# PiPod_Rev2.net
KiCad netlist of a schematic drawn in EAGLE
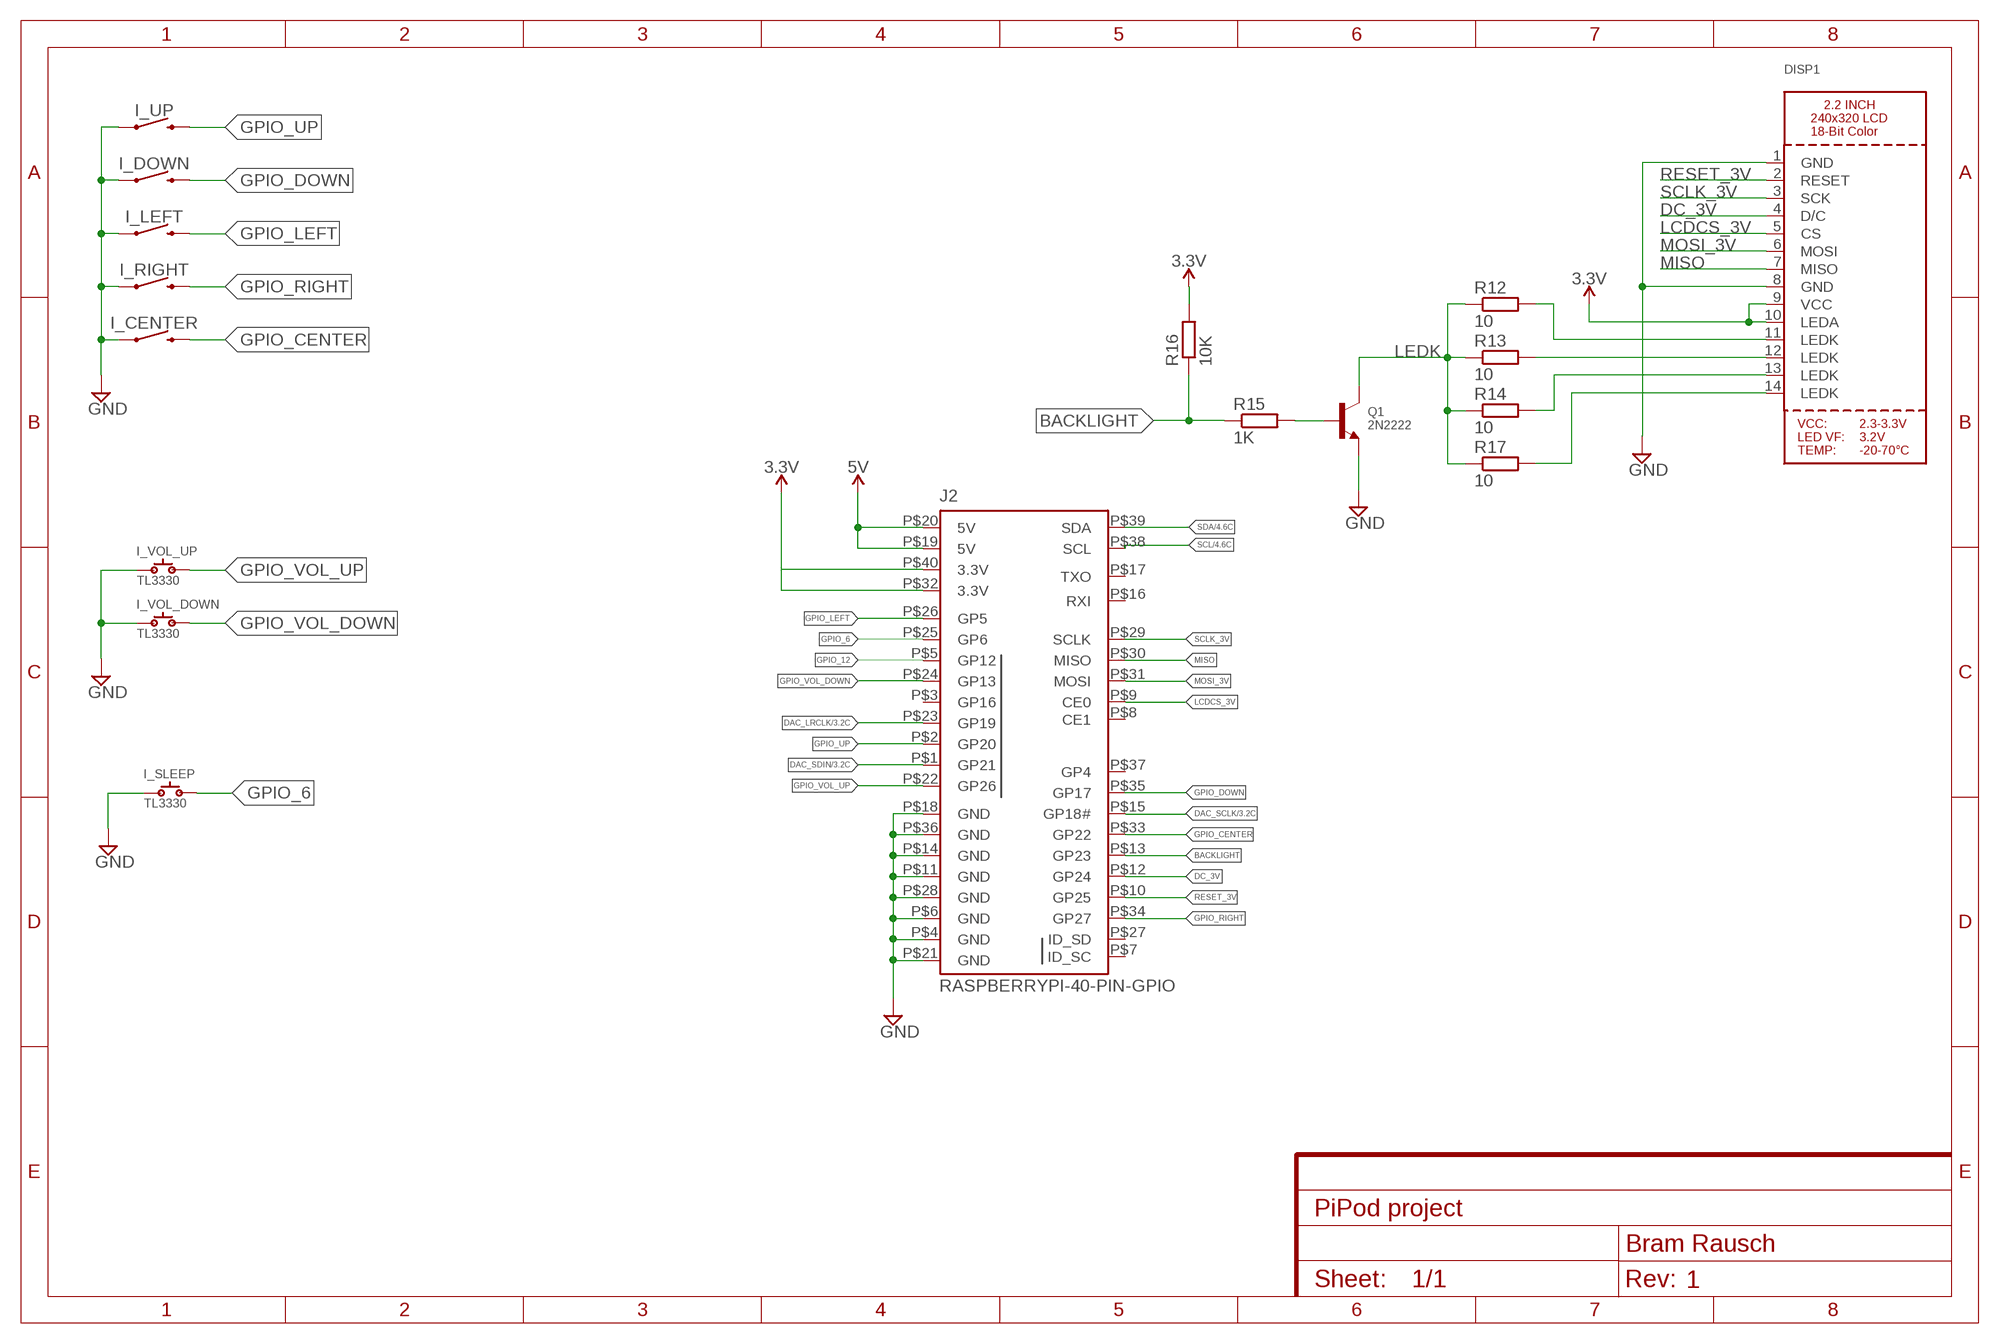
[diagram p0: schematic, sheet 1]
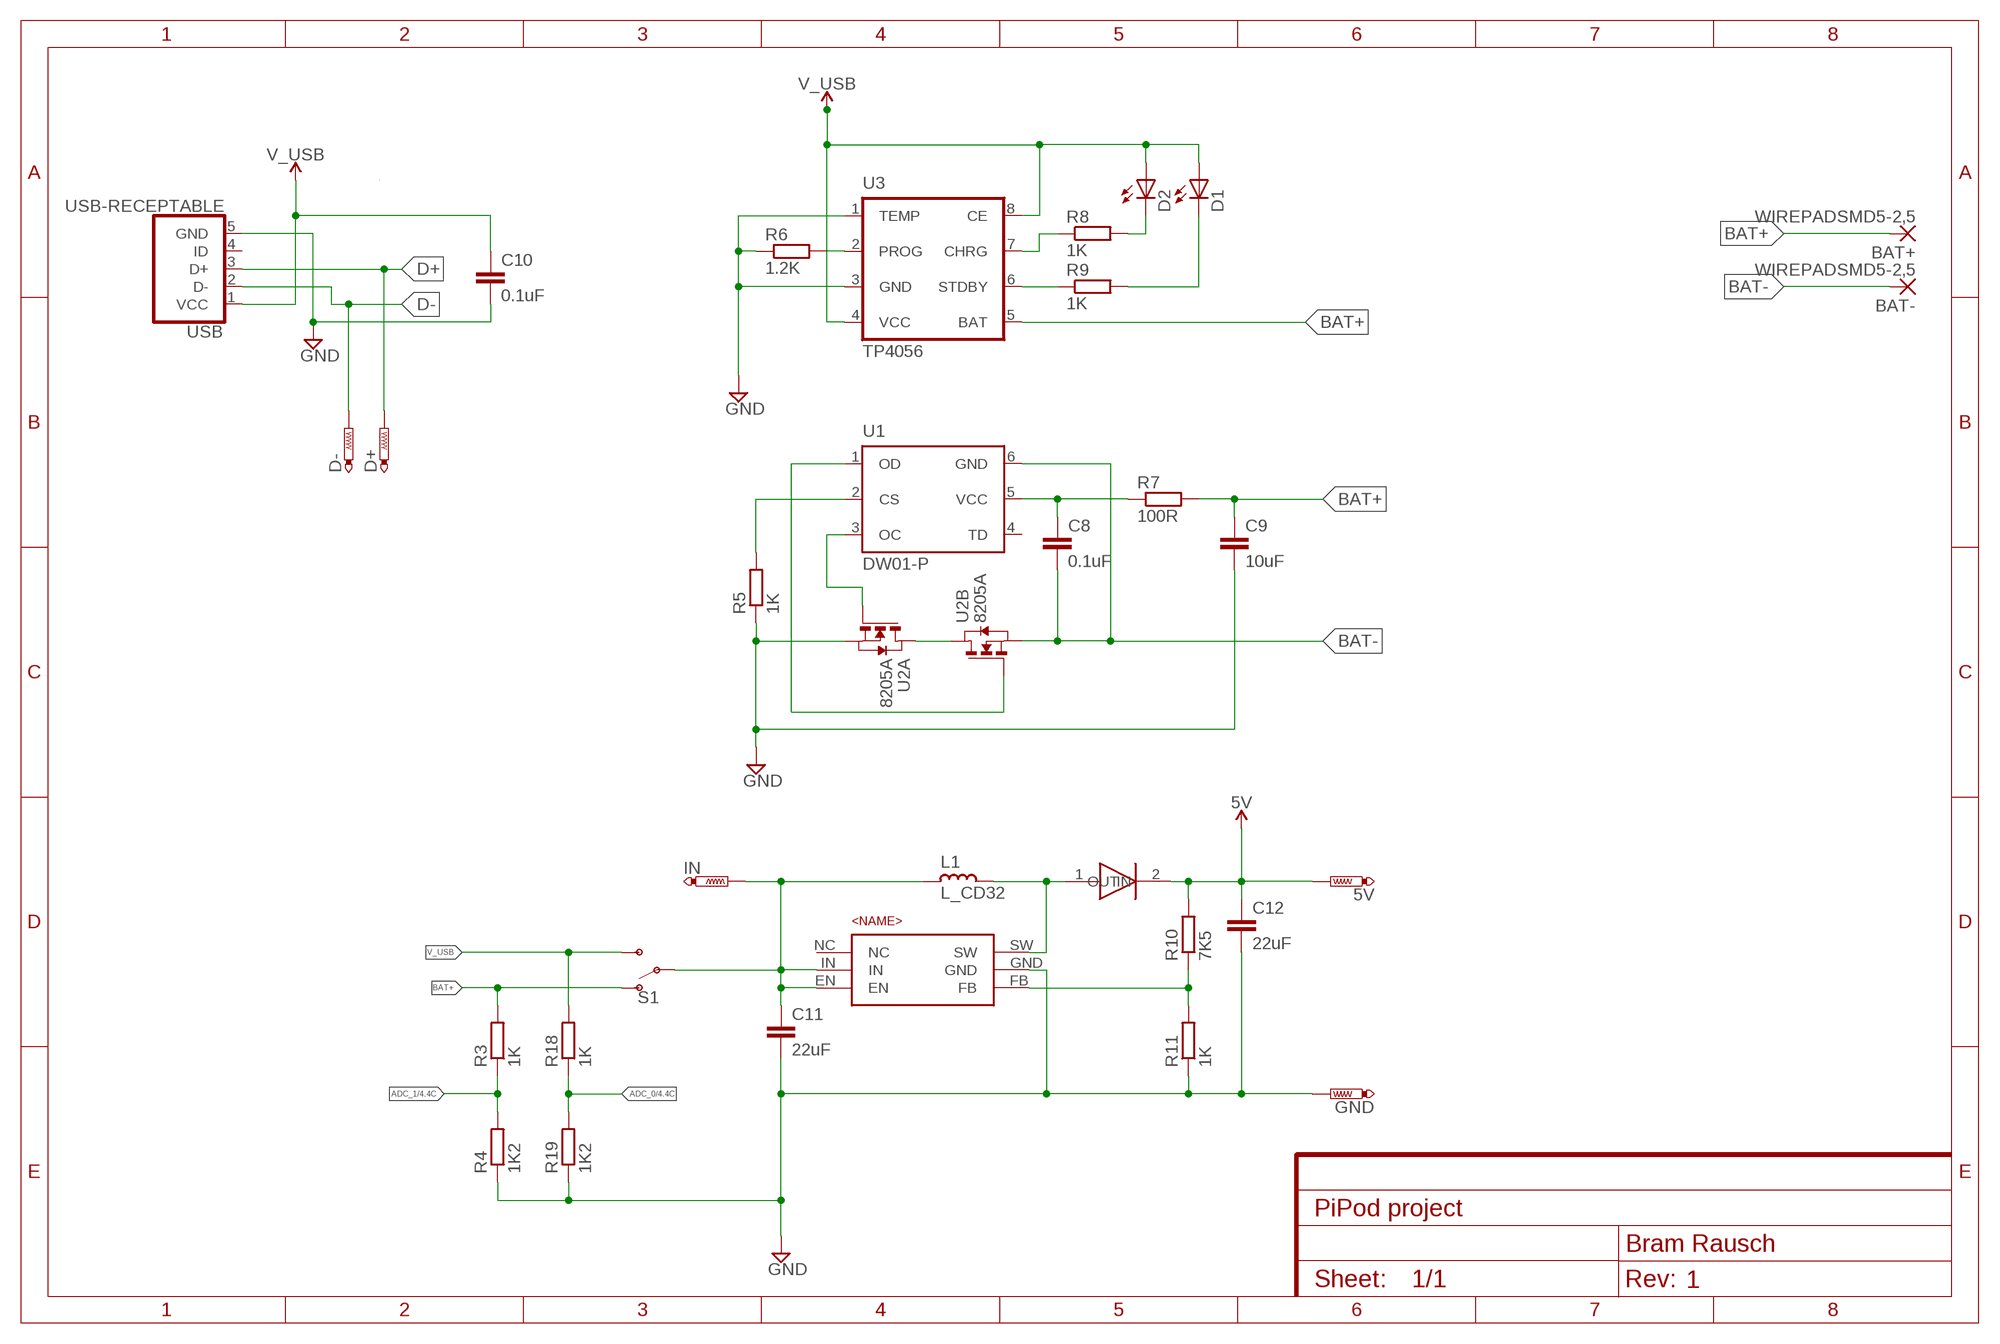
[diagram p1: schematic, sheet 2]
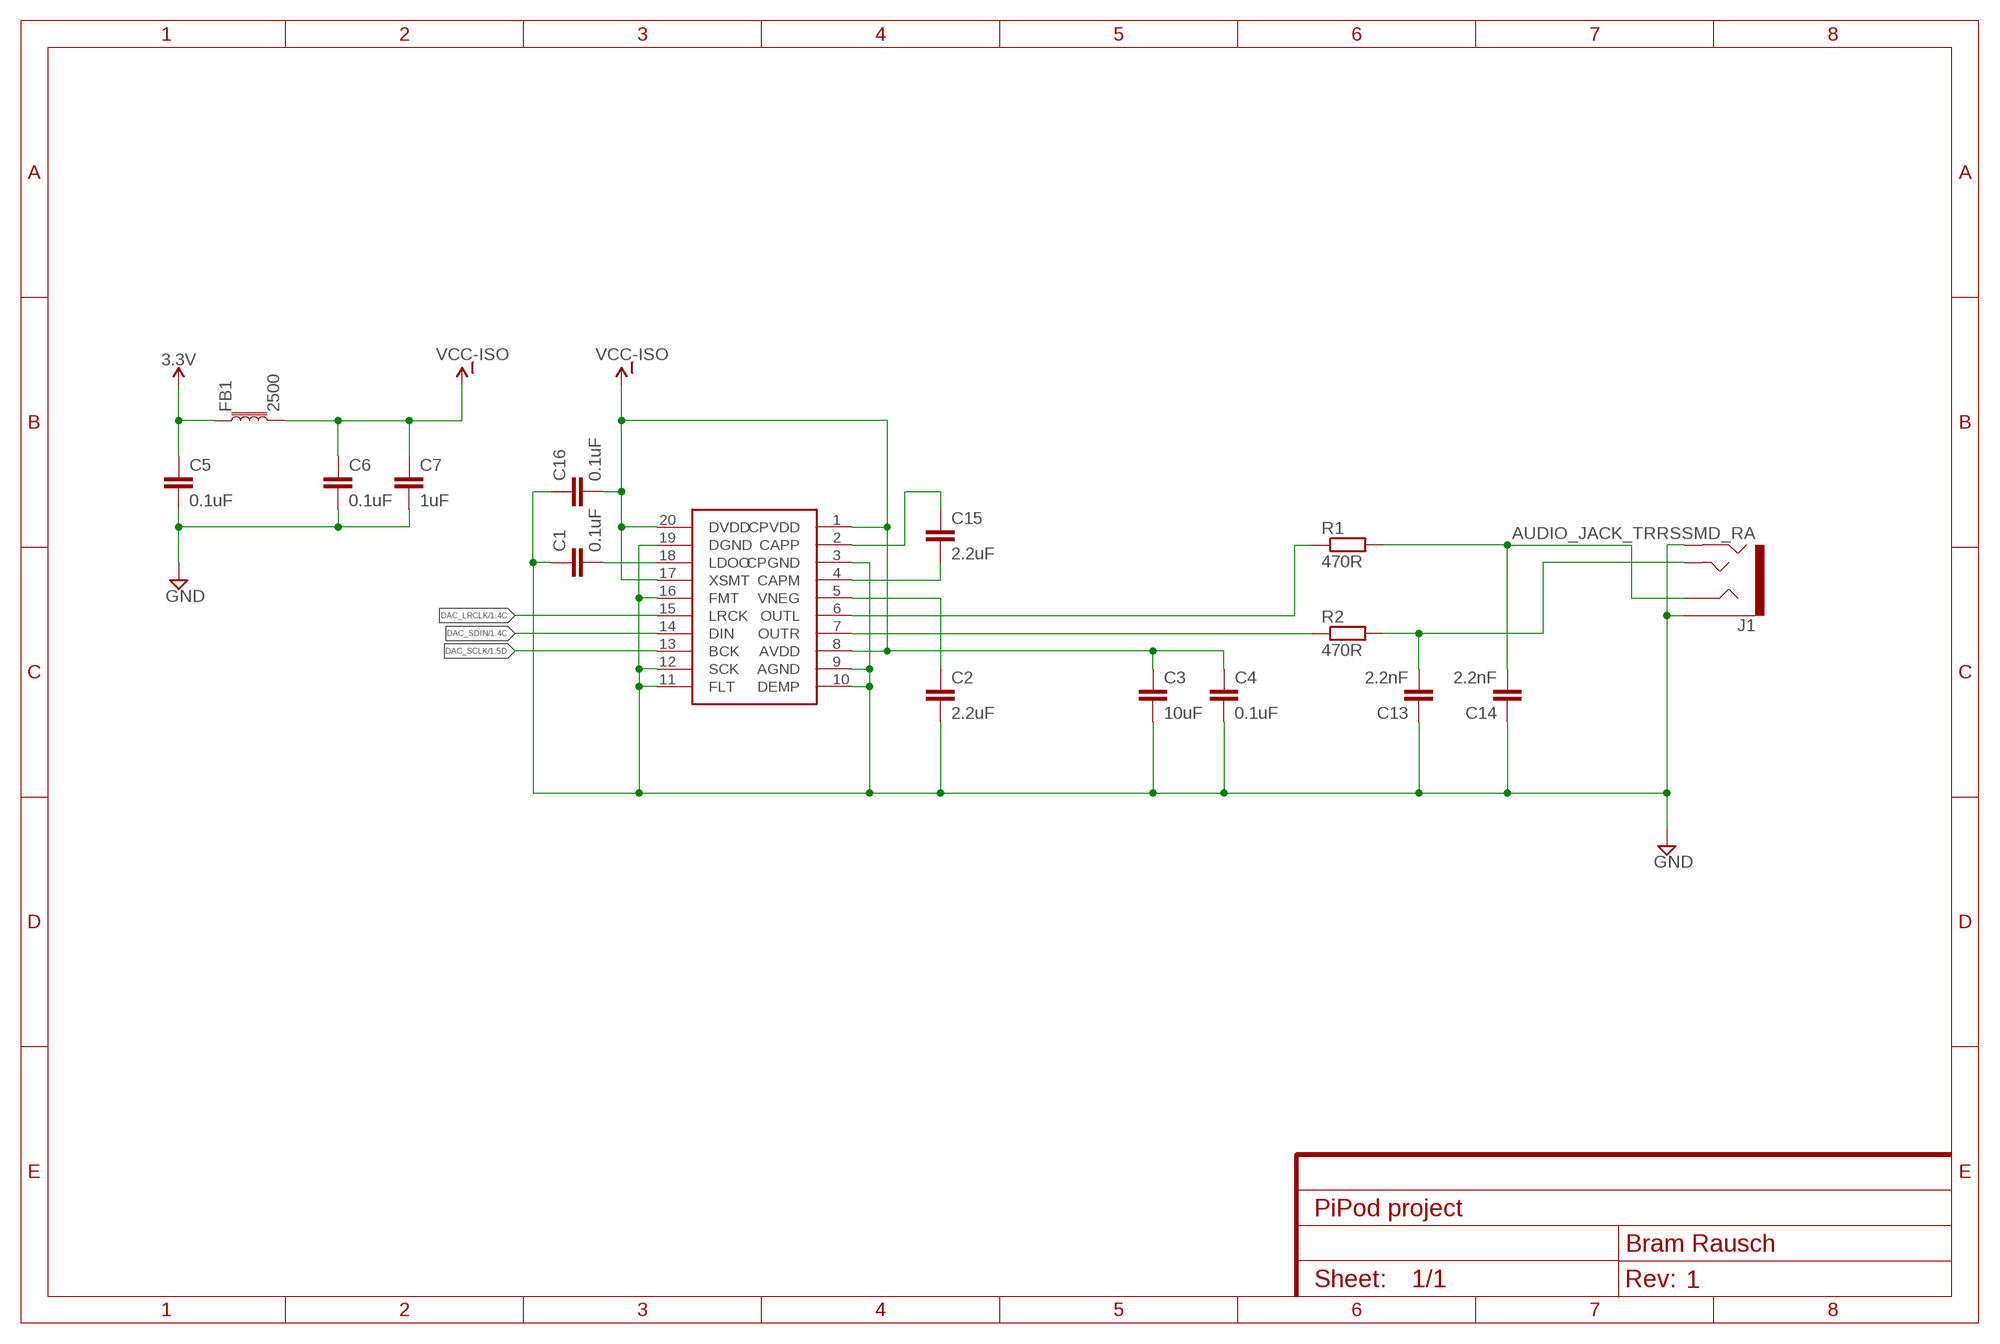
[diagram p2: schematic, sheet 3]
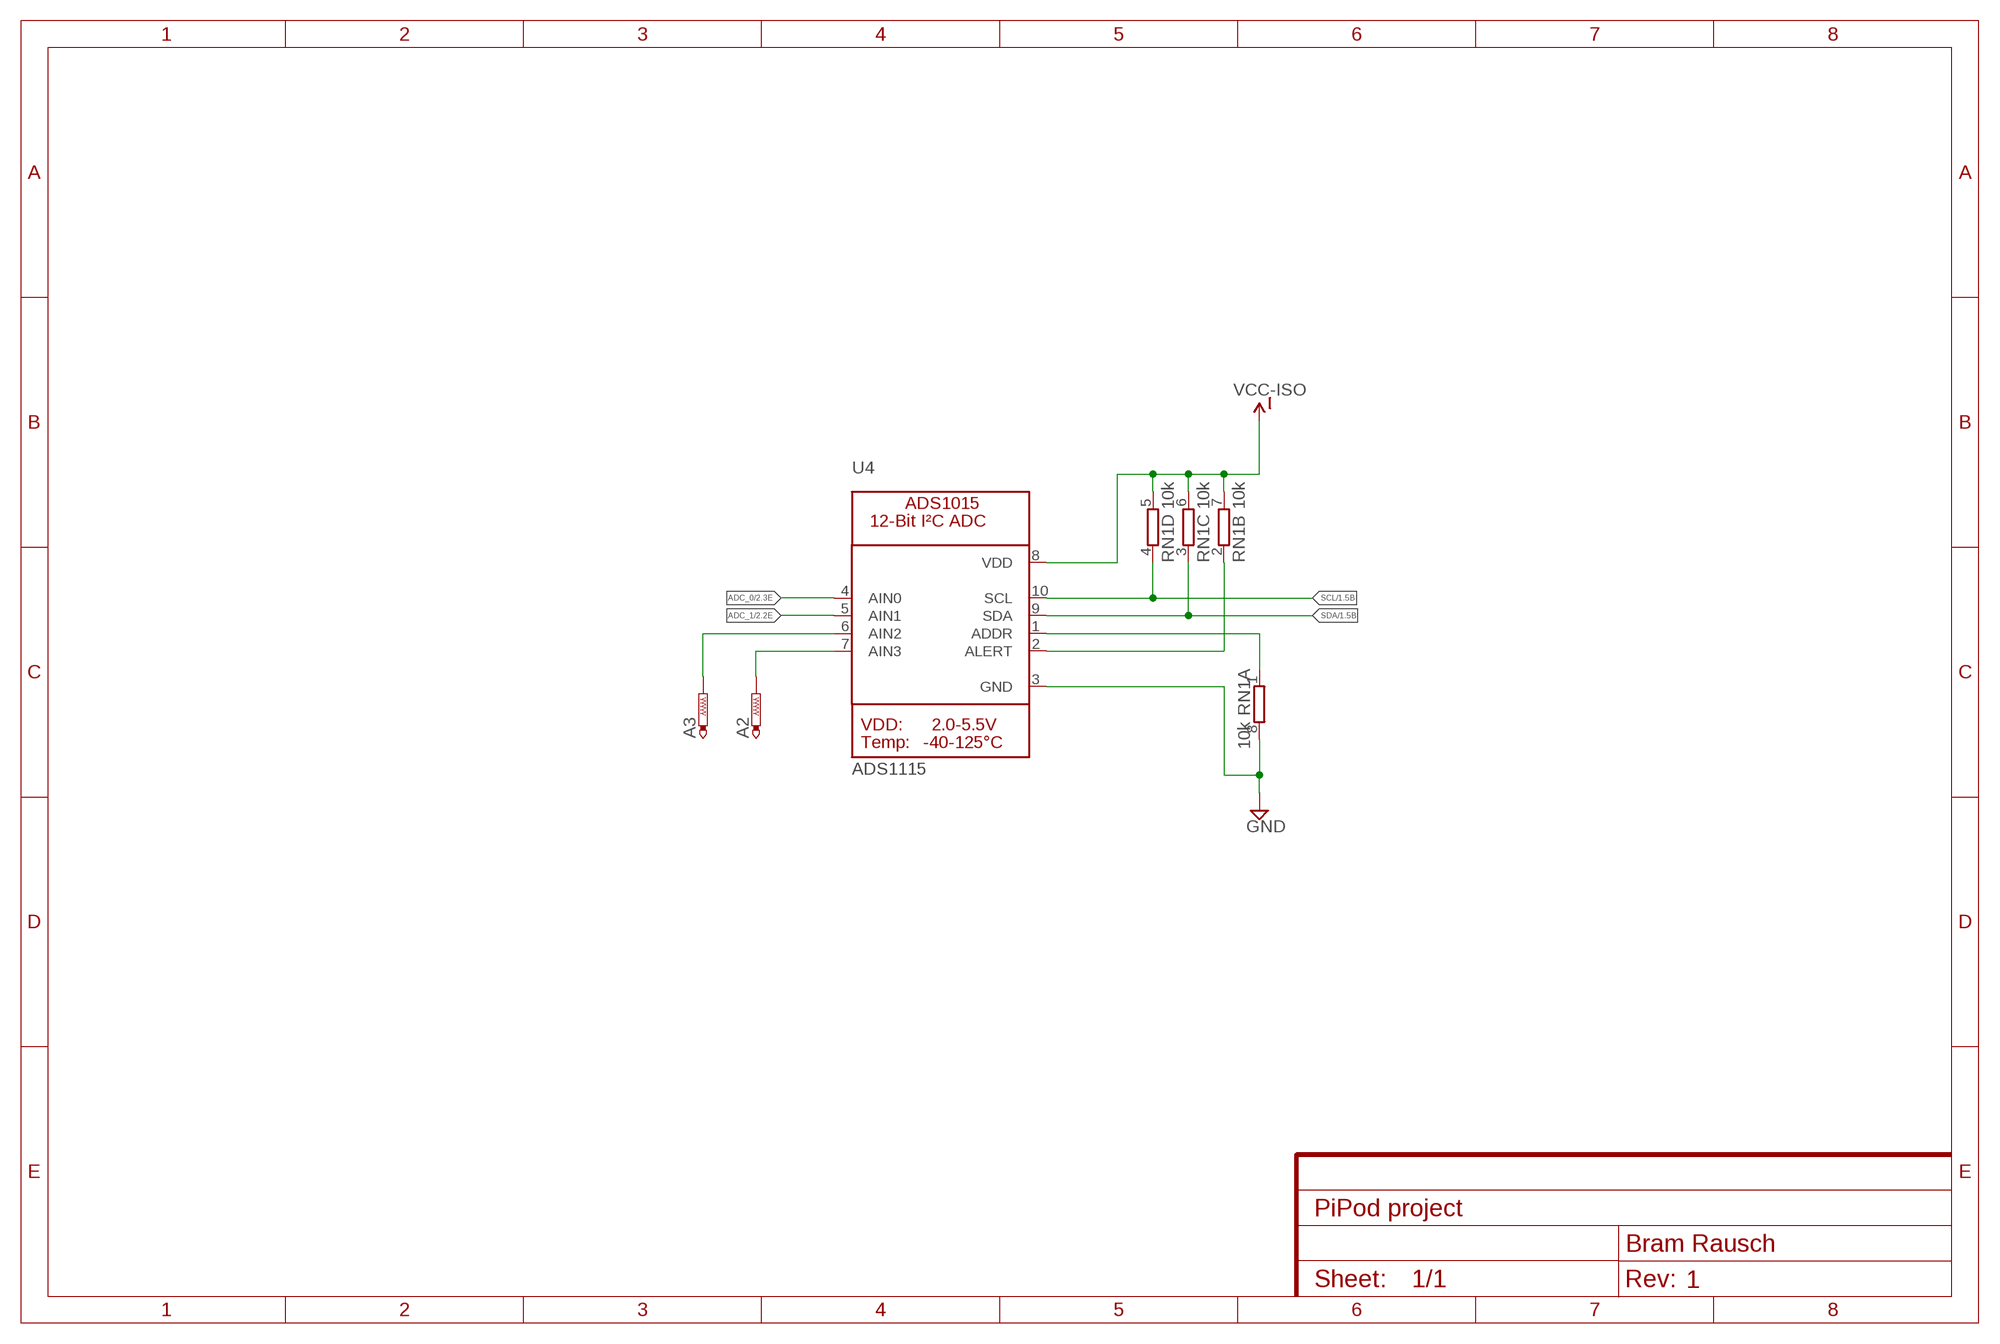
[diagram p3: schematic, sheet 4]

(export (version "E")
  (design (tool "Eeschema 10.0.6"))
  (components
    (comp (ref "A2")
      (value "PTR1TP15R")
      (footprint "eagle-import:TP15R")
      (libsource (lib "eagle-import") (part "PTR1TP15R"))
    )
    (comp (ref "A3")
      (value "PTR1TP15R")
      (footprint "eagle-import:TP15R")
      (libsource (lib "eagle-import") (part "PTR1TP15R"))
    )
    (comp (ref "RN1")
      (value "10k")
      (footprint "eagle-import:0603-ARC")
      (libsource (lib "eagle-import") (part "4R-N0603-ARC"))
    )
    (comp (ref "U4")
      (value "ADS1115")
      (footprint "eagle-import:MICROBUILDER_MSOP10")
      (libsource (lib "eagle-import") (part "MICROBUILDER_ADC_ADS1015"))
    )
    (comp (ref "5V")
      (value "PTR1B2,54")
      (footprint "eagle-import:B2,54")
      (libsource (lib "eagle-import") (part "PTR1B2,54"))
    )
    (comp (ref "BAT+")
      (value "WIREPADSMD5-2,5")
      (footprint "eagle-import:5-2,5")
      (libsource (lib "eagle-import") (part "WIREPADSMD5-2,5"))
    )
    (comp (ref "BAT-")
      (value "WIREPADSMD5-2,5")
      (footprint "eagle-import:5-2,5")
      (libsource (lib "eagle-import") (part "WIREPADSMD5-2,5"))
    )
    (comp (ref "C8")
      (value "0.1uF")
      (footprint "eagle-import:C1206K")
      (libsource (lib "eagle-import") (part "resistor_348_C-EUC1206K"))
    )
    (comp (ref "C9")
      (value "10uF")
      (footprint "eagle-import:C1206K")
      (libsource (lib "eagle-import") (part "resistor_348_C-EUC1206K"))
    )
    (comp (ref "C10")
      (value "0.1uF")
      (footprint "eagle-import:C1206K")
      (libsource (lib "eagle-import") (part "resistor_348_C-EUC1206K"))
    )
    (comp (ref "C11")
      (value "22uF")
      (footprint "eagle-import:C0805K")
      (libsource (lib "eagle-import") (part "resistor_348_C-EUC0805K"))
    )
    (comp (ref "C12")
      (value "22uF")
      (footprint "eagle-import:C0805K")
      (libsource (lib "eagle-import") (part "resistor_348_C-EUC0805K"))
    )
    (comp (ref "D+")
      (value "PTR1TP15R")
      (footprint "eagle-import:TP15R")
      (libsource (lib "eagle-import") (part "PTR1TP15R"))
    )
    (comp (ref "D-")
      (value "PTR1TP15R")
      (footprint "eagle-import:TP15R")
      (libsource (lib "eagle-import") (part "PTR1TP15R"))
    )
    (comp (ref "D1")
      (value "LEDCHIPLED_0805")
      (footprint "eagle-import:CHIPLED_0805")
      (libsource (lib "eagle-import") (part "LEDCHIPLED_0805"))
    )
    (comp (ref "D2")
      (value "LEDCHIPLED_0805")
      (footprint "eagle-import:CHIPLED_0805")
      (libsource (lib "eagle-import") (part "LEDCHIPLED_0805"))
    )
    (comp (ref "GND")
      (value "PTR1B2,54")
      (footprint "eagle-import:B2,54")
      (libsource (lib "eagle-import") (part "PTR1B2,54"))
    )
    (comp (ref "IN")
      (value "PTR1B2,54")
      (footprint "eagle-import:B2,54")
      (libsource (lib "eagle-import") (part "PTR1B2,54"))
    )
    (comp (ref "L1")
      (value "L_CD32")
      (footprint "eagle-import:CD32")
      (libsource (lib "eagle-import") (part "L_CD32"))
    )
    (comp (ref "R3")
      (value "1K")
      (footprint "eagle-import:R0805")
      (libsource (lib "eagle-import") (part "R-EU_R0805"))
    )
    (comp (ref "R4")
      (value "1K2")
      (footprint "eagle-import:R0805")
      (libsource (lib "eagle-import") (part "R-EU_R0805"))
    )
    (comp (ref "R5")
      (value "1K")
      (footprint "eagle-import:M0805")
      (libsource (lib "eagle-import") (part "R-EU_M0805"))
    )
    (comp (ref "R6")
      (value "1.2K")
      (footprint "eagle-import:M0805")
      (libsource (lib "eagle-import") (part "R-EU_M0805"))
    )
    (comp (ref "R7")
      (value "100R")
      (footprint "eagle-import:M0805")
      (libsource (lib "eagle-import") (part "R-EU_M0805"))
    )
    (comp (ref "R8")
      (value "1K")
      (footprint "eagle-import:M0805")
      (libsource (lib "eagle-import") (part "R-EU_M0805"))
    )
    (comp (ref "R9")
      (value "1K")
      (footprint "eagle-import:M0805")
      (libsource (lib "eagle-import") (part "R-EU_M0805"))
    )
    (comp (ref "R10")
      (value "7K5")
      (footprint "eagle-import:R0805")
      (libsource (lib "eagle-import") (part "R-EU_R0805"))
    )
    (comp (ref "R11")
      (value "1K")
      (footprint "eagle-import:R0805")
      (libsource (lib "eagle-import") (part "R-EU_R0805"))
    )
    (comp (ref "R18")
      (value "1K")
      (footprint "eagle-import:R0805")
      (libsource (lib "eagle-import") (part "R-EU_R0805"))
    )
    (comp (ref "R19")
      (value "1K2")
      (footprint "eagle-import:R0805")
      (libsource (lib "eagle-import") (part "R-EU_R0805"))
    )
    (comp (ref "S1")
      (value "SWITCH-SPDT-PTH-11.6X4.0MM")
      (footprint "eagle-import:SWITCH_SPDT_PTH_11.6X4.0MM")
      (libsource (lib "eagle-import") (part "SWITCH-SPDT-PTH-11.6X4.0MM"))
    )
    (comp (ref "U$9")
      (value "SMA-SS34")
      (footprint "eagle-import:SMA-SS34")
      (libsource (lib "eagle-import") (part "SMA-SS34"))
    )
    (comp (ref "U1")
      (value "DW01-P")
      (footprint "eagle-import:SOT23-6L")
      (libsource (lib "eagle-import") (part "DW01-P"))
    )
    (comp (ref "U2")
      (value "8205A")
      (footprint "eagle-import:TSSOP8")
      (libsource (lib "eagle-import") (part "8205A"))
    )
    (comp (ref "U3")
      (value "TP4056")
      (footprint "eagle-import:SO08")
      (libsource (lib "eagle-import") (part "TP4056"))
    )
    (comp (ref "U6")
      (value "MT3608")
      (footprint "eagle-import:SOT23-6")
      (libsource (lib "eagle-import") (part "MT3608"))
    )
    (comp (ref "USB")
      (value "USB-RECEPTABLE")
      (footprint "eagle-import:FCI-10103594-0001LF")
      (libsource (lib "eagle-import") (part "USB-RECEPTABLE"))
    )
    (comp (ref "C1")
      (value "0.1uF")
      (footprint "eagle-import:C0805K")
      (libsource (lib "eagle-import") (part "C-EUC0805K"))
    )
    (comp (ref "C2")
      (value "2.2uF")
      (footprint "eagle-import:C0805K")
      (libsource (lib "eagle-import") (part "C-EUC0805K"))
    )
    (comp (ref "C3")
      (value "10uF")
      (footprint "eagle-import:C0805K")
      (libsource (lib "eagle-import") (part "C-EUC0805K"))
    )
    (comp (ref "C4")
      (value "0.1uF")
      (footprint "eagle-import:C0805K")
      (libsource (lib "eagle-import") (part "C-EUC0805K"))
    )
    (comp (ref "C5")
      (value "0.1uF")
      (footprint "eagle-import:C0805K")
      (libsource (lib "eagle-import") (part "C-EUC0805K"))
    )
    (comp (ref "C6")
      (value "0.1uF")
      (footprint "eagle-import:C0805K")
      (libsource (lib "eagle-import") (part "C-EUC0805K"))
    )
    (comp (ref "C7")
      (value "1uF")
      (footprint "eagle-import:C0805K")
      (libsource (lib "eagle-import") (part "C-EUC0805K"))
    )
    (comp (ref "C13")
      (value "2.2nF")
      (footprint "eagle-import:C0805K")
      (libsource (lib "eagle-import") (part "C-EUC0805K"))
    )
    (comp (ref "C14")
      (value "2.2nF")
      (footprint "eagle-import:C0805K")
      (libsource (lib "eagle-import") (part "C-EUC0805K"))
    )
    (comp (ref "C15")
      (value "2.2uF")
      (footprint "eagle-import:C0805K")
      (libsource (lib "eagle-import") (part "C-EUC0805K"))
    )
    (comp (ref "C16")
      (value "0.1uF")
      (footprint "eagle-import:C0805K")
      (libsource (lib "eagle-import") (part "C-EUC0805K"))
    )
    (comp (ref "FB1")
      (value "2500")
      (footprint "eagle-import:0603")
      (libsource (lib "eagle-import") (part "FERRITE_BEAD-0603"))
    )
    (comp (ref "J1")
      (value "AUDIO_JACK_TRRSSMD_RA")
      (footprint "eagle-import:AUDIO_JACK_3.5MM_TRRS_SMD_RA")
      (libsource (lib "eagle-import") (part "AUDIO_JACK_TRRSSMD_RA"))
    )
    (comp (ref "R1")
      (value "470R")
      (footprint "eagle-import:R0805")
      (libsource (lib "eagle-import") (part "R-EU_R0805"))
    )
    (comp (ref "R2")
      (value "470R")
      (footprint "eagle-import:R0805")
      (libsource (lib "eagle-import") (part "R-EU_R0805"))
    )
    (comp (ref "U5")
      (value "PCM5102")
      (footprint "eagle-import:TSSOP20")
      (libsource (lib "eagle-import") (part "PCM5102"))
    )
    (comp (ref "DISP1")
      (value "DISP_LCD_TM022HDH26")
      (footprint "eagle-import:TM022HDH26_2.2IN_LCD")
      (libsource (lib "eagle-import") (part "DISP_LCD_TM022HDH26"))
    )
    (comp (ref "I_CENTER")
      (value "MOMENTARY-SWITCH-SPST-SMD-5.2-REDUNDANT")
      (footprint "eagle-import:TACTILE_SWITCH_SMD_5.2MM")
      (libsource (lib "eagle-import") (part "MOMENTARY-SWITCH-SPST-SMD-5.2-REDUNDANT"))
    )
    (comp (ref "I_DOWN")
      (value "MOMENTARY-SWITCH-SPST-SMD-5.2-REDUNDANT")
      (footprint "eagle-import:TACTILE_SWITCH_SMD_5.2MM")
      (libsource (lib "eagle-import") (part "MOMENTARY-SWITCH-SPST-SMD-5.2-REDUNDANT"))
    )
    (comp (ref "I_LEFT")
      (value "MOMENTARY-SWITCH-SPST-SMD-5.2-REDUNDANT")
      (footprint "eagle-import:TACTILE_SWITCH_SMD_5.2MM")
      (libsource (lib "eagle-import") (part "MOMENTARY-SWITCH-SPST-SMD-5.2-REDUNDANT"))
    )
    (comp (ref "I_RIGHT")
      (value "MOMENTARY-SWITCH-SPST-SMD-5.2-REDUNDANT")
      (footprint "eagle-import:TACTILE_SWITCH_SMD_5.2MM")
      (libsource (lib "eagle-import") (part "MOMENTARY-SWITCH-SPST-SMD-5.2-REDUNDANT"))
    )
    (comp (ref "I_SLEEP")
      (value "TL3330")
      (footprint "eagle-import:TL3330")
      (libsource (lib "eagle-import") (part "TL3330"))
    )
    (comp (ref "I_UP")
      (value "MOMENTARY-SWITCH-SPST-SMD-5.2-REDUNDANT")
      (footprint "eagle-import:TACTILE_SWITCH_SMD_5.2MM")
      (libsource (lib "eagle-import") (part "MOMENTARY-SWITCH-SPST-SMD-5.2-REDUNDANT"))
    )
    (comp (ref "I_VOL_DOWN")
      (value "TL3330")
      (footprint "eagle-import:TL3330")
      (libsource (lib "eagle-import") (part "TL3330"))
    )
    (comp (ref "I_VOL_UP")
      (value "TL3330")
      (footprint "eagle-import:TL3330")
      (libsource (lib "eagle-import") (part "TL3330"))
    )
    (comp (ref "J2")
      (value "RASPBERRYPI-40-PIN-GPIO")
      (footprint "eagle-import:2X20_SMD")
      (libsource (lib "eagle-import") (part "RASPBERRYPI-40-PIN-GPIO"))
    )
    (comp (ref "Q1")
      (value "2N2222")
      (footprint "eagle-import:SOT23-WIDE")
      (libsource (lib "eagle-import") (part "TRANSISTOR_NPNWIDE"))
    )
    (comp (ref "R12")
      (value "10")
      (footprint "eagle-import:R0805")
      (libsource (lib "eagle-import") (part "R-EU_R0805"))
    )
    (comp (ref "R13")
      (value "10")
      (footprint "eagle-import:R0805")
      (libsource (lib "eagle-import") (part "R-EU_R0805"))
    )
    (comp (ref "R14")
      (value "10")
      (footprint "eagle-import:R0805")
      (libsource (lib "eagle-import") (part "R-EU_R0805"))
    )
    (comp (ref "R15")
      (value "1K")
      (footprint "eagle-import:R0805")
      (libsource (lib "eagle-import") (part "R-EU_R0805"))
    )
    (comp (ref "R16")
      (value "10K")
      (footprint "eagle-import:R0805")
      (libsource (lib "eagle-import") (part "R-EU_R0805"))
    )
    (comp (ref "R17")
      (value "10")
      (footprint "eagle-import:R0805")
      (libsource (lib "eagle-import") (part "R-EU_R0805"))
    )
  )
  (nets
    (net (code "1") (name "3.3V") (class "Default")
      (node (ref "C5") (pin "1") (pinfunction "1_1") (pintype "passive"))
      (node (ref "DISP1") (pin "10") (pinfunction "LEDA_10") (pintype "power_in"))
      (node (ref "DISP1") (pin "9") (pinfunction "VCC_9") (pintype "power_in"))
      (node (ref "FB1") (pin "1") (pinfunction "1_1") (pintype "passive"))
      (node (ref "J2") (pin "P$32") (pinfunction "3.3V_P$32") (pintype "power_in"))
      (node (ref "J2") (pin "P$40") (pinfunction "3.3V_P$40") (pintype "power_in"))
      (node (ref "R16") (pin "2") (pinfunction "2_2") (pintype "passive"))
    )
    (net (code "2") (name "5V") (class "Default")
      (node (ref "5V") (pin "TP") (pinfunction "TP_TP") (pintype "input"))
      (node (ref "C12") (pin "1") (pinfunction "1_1") (pintype "passive"))
      (node (ref "J2") (pin "P$19") (pinfunction "5V_P$19") (pintype "power_in"))
      (node (ref "J2") (pin "P$20") (pinfunction "5V_P$20") (pintype "power_in"))
      (node (ref "R10") (pin "2") (pinfunction "2_2") (pintype "passive"))
      (node (ref "U$9") (pin "2") (pinfunction "OUT_2") (pintype "bidirectional"))
    )
    (net (code "3") (name "ADC_0") (class "Default")
      (node (ref "R18") (pin "1") (pinfunction "1_1") (pintype "passive"))
      (node (ref "R19") (pin "2") (pinfunction "2_2") (pintype "passive"))
      (node (ref "U4") (pin "4") (pinfunction "AIN0_4") (pintype "bidirectional"))
    )
    (net (code "4") (name "ADC_1") (class "Default")
      (node (ref "R3") (pin "1") (pinfunction "1_1") (pintype "passive"))
      (node (ref "R4") (pin "2") (pinfunction "2_2") (pintype "passive"))
      (node (ref "U4") (pin "5") (pinfunction "AIN1_5") (pintype "bidirectional"))
    )
    (net (code "5") (name "BACKLIGHT") (class "Default")
      (node (ref "J2") (pin "P$13") (pinfunction "GP23_P$13") (pintype "bidirectional"))
      (node (ref "R15") (pin "1") (pinfunction "1_1") (pintype "passive"))
      (node (ref "R16") (pin "1") (pinfunction "1_1") (pintype "passive"))
    )
    (net (code "6") (name "BAT+") (class "Default")
      (node (ref "BAT+") (pin "1") (pinfunction "P_1") (pintype "passive"))
      (node (ref "C9") (pin "1") (pinfunction "1_1") (pintype "passive"))
      (node (ref "R3") (pin "2") (pinfunction "2_2") (pintype "passive"))
      (node (ref "R7") (pin "2") (pinfunction "2_2") (pintype "passive"))
      (node (ref "S1") (pin "1") (pinfunction "O_1") (pintype "passive"))
      (node (ref "U3") (pin "5") (pinfunction "BAT_5") (pintype "input"))
    )
    (net (code "7") (name "BAT-") (class "Default")
      (node (ref "BAT-") (pin "1") (pinfunction "P_1") (pintype "passive"))
      (node (ref "C8") (pin "2") (pinfunction "2_2") (pintype "passive"))
      (node (ref "U1") (pin "6") (pinfunction "GND_6") (pintype "output"))
      (node (ref "U2") (pin "6") (pinfunction "S_6") (pintype "passive"))
      (node (ref "U2") (pin "7") (pinfunction "S_7") (pintype "passive"))
    )
    (net (code "8") (name "D+") (class "Default")
      (node (ref "D+") (pin "TP") (pinfunction "TP_TP") (pintype "input"))
      (node (ref "USB") (pin "3") (pinfunction "D+_3") (pintype "bidirectional"))
    )
    (net (code "9") (name "D-") (class "Default")
      (node (ref "D-") (pin "TP") (pinfunction "TP_TP") (pintype "input"))
      (node (ref "USB") (pin "2") (pinfunction "D-_2") (pintype "bidirectional"))
    )
    (net (code "10") (name "DAC_LRCLK") (class "Default")
      (node (ref "J2") (pin "P$23") (pinfunction "GP19_P$23") (pintype "bidirectional"))
      (node (ref "U5") (pin "15") (pinfunction "LRCK_15") (pintype "bidirectional"))
    )
    (net (code "11") (name "DAC_SCLK") (class "Default")
      (node (ref "J2") (pin "P$15") (pinfunction "GP18#_P$15") (pintype "bidirectional"))
      (node (ref "U5") (pin "13") (pinfunction "BCK_13") (pintype "bidirectional"))
    )
    (net (code "12") (name "DAC_SDIN") (class "Default")
      (node (ref "J2") (pin "P$1") (pinfunction "GP21_P$1") (pintype "bidirectional"))
      (node (ref "U5") (pin "14") (pinfunction "DIN_14") (pintype "bidirectional"))
    )
    (net (code "13") (name "DC_3V") (class "Default")
      (node (ref "DISP1") (pin "4") (pinfunction "D/C_4") (pintype "input"))
      (node (ref "J2") (pin "P$12") (pinfunction "GP24_P$12") (pintype "bidirectional"))
    )
    (net (code "14") (name "GND") (class "Default")
      (node (ref "C1") (pin "1") (pinfunction "1_1") (pintype "passive"))
      (node (ref "C10") (pin "2") (pinfunction "2_2") (pintype "passive"))
      (node (ref "C11") (pin "2") (pinfunction "2_2") (pintype "passive"))
      (node (ref "C12") (pin "2") (pinfunction "2_2") (pintype "passive"))
      (node (ref "C13") (pin "1") (pinfunction "1_1") (pintype "passive"))
      (node (ref "C14") (pin "1") (pinfunction "1_1") (pintype "passive"))
      (node (ref "C16") (pin "1") (pinfunction "1_1") (pintype "passive"))
      (node (ref "C2") (pin "2") (pinfunction "2_2") (pintype "passive"))
      (node (ref "C3") (pin "2") (pinfunction "2_2") (pintype "passive"))
      (node (ref "C4") (pin "2") (pinfunction "2_2") (pintype "passive"))
      (node (ref "C5") (pin "2") (pinfunction "2_2") (pintype "passive"))
      (node (ref "C6") (pin "2") (pinfunction "2_2") (pintype "passive"))
      (node (ref "C7") (pin "2") (pinfunction "2_2") (pintype "passive"))
      (node (ref "C9") (pin "2") (pinfunction "2_2") (pintype "passive"))
      (node (ref "DISP1") (pin "1") (pinfunction "GND_1") (pintype "power_in"))
      (node (ref "DISP1") (pin "8") (pinfunction "GND_8") (pintype "power_in"))
      (node (ref "GND") (pin "TP") (pinfunction "TP_TP") (pintype "input"))
      (node (ref "I_CENTER") (pin "1") (pinfunction "1_1") (pintype "passive"))
      (node (ref "I_CENTER") (pin "2") (pinfunction "1_2") (pintype "passive"))
      (node (ref "I_DOWN") (pin "1") (pinfunction "1_1") (pintype "passive"))
      (node (ref "I_DOWN") (pin "2") (pinfunction "1_2") (pintype "passive"))
      (node (ref "I_LEFT") (pin "1") (pinfunction "1_1") (pintype "passive"))
      (node (ref "I_LEFT") (pin "2") (pinfunction "1_2") (pintype "passive"))
      (node (ref "I_RIGHT") (pin "1") (pinfunction "1_1") (pintype "passive"))
      (node (ref "I_RIGHT") (pin "2") (pinfunction "1_2") (pintype "passive"))
      (node (ref "I_SLEEP") (pin "1") (pinfunction "1_1") (pintype "bidirectional"))
      (node (ref "I_UP") (pin "1") (pinfunction "1_1") (pintype "passive"))
      (node (ref "I_UP") (pin "2") (pinfunction "1_2") (pintype "passive"))
      (node (ref "I_VOL_DOWN") (pin "1") (pinfunction "1_1") (pintype "bidirectional"))
      (node (ref "I_VOL_UP") (pin "1") (pinfunction "1_1") (pintype "bidirectional"))
      (node (ref "J1") (pin "EARTH") (pinfunction "EARTH_EARTH") (pintype "bidirectional"))
      (node (ref "J1") (pin "RING2") (pinfunction "RING2_RING2") (pintype "bidirectional"))
      (node (ref "J2") (pin "P$11") (pinfunction "GND_P$11") (pintype "power_in"))
      (node (ref "J2") (pin "P$14") (pinfunction "GND_P$14") (pintype "power_in"))
      (node (ref "J2") (pin "P$18") (pinfunction "GND_P$18") (pintype "power_in"))
      (node (ref "J2") (pin "P$21") (pinfunction "GND_P$21") (pintype "power_in"))
      (node (ref "J2") (pin "P$28") (pinfunction "GND_P$28") (pintype "power_in"))
      (node (ref "J2") (pin "P$36") (pinfunction "GND_P$36") (pintype "power_in"))
      (node (ref "J2") (pin "P$4") (pinfunction "GND_P$4") (pintype "power_in"))
      (node (ref "J2") (pin "P$6") (pinfunction "GND_P$6") (pintype "power_in"))
      (node (ref "Q1") (pin "2") (pinfunction "E_2") (pintype "passive"))
      (node (ref "R11") (pin "1") (pinfunction "1_1") (pintype "passive"))
      (node (ref "R19") (pin "1") (pinfunction "1_1") (pintype "passive"))
      (node (ref "R4") (pin "1") (pinfunction "1_1") (pintype "passive"))
      (node (ref "R5") (pin "1") (pinfunction "1_1") (pintype "passive"))
      (node (ref "R6") (pin "1") (pinfunction "1_1") (pintype "passive"))
      (node (ref "RN1") (pin "8") (pinfunction "2_8") (pintype "passive"))
      (node (ref "U2") (pin "2") (pinfunction "S_2") (pintype "passive"))
      (node (ref "U2") (pin "3") (pinfunction "S_3") (pintype "passive"))
      (node (ref "U3") (pin "1") (pinfunction "TEMP_1") (pintype "power_in"))
      (node (ref "U3") (pin "3") (pinfunction "GND_3") (pintype "output"))
      (node (ref "U4") (pin "3") (pinfunction "GND_3") (pintype "bidirectional"))
      (node (ref "U5") (pin "10") (pinfunction "DEMP_10") (pintype "bidirectional"))
      (node (ref "U5") (pin "11") (pinfunction "FLT_11") (pintype "bidirectional"))
      (node (ref "U5") (pin "12") (pinfunction "SCK_12") (pintype "bidirectional"))
      (node (ref "U5") (pin "16") (pinfunction "FMT_16") (pintype "bidirectional"))
      (node (ref "U5") (pin "19") (pinfunction "DGND_19") (pintype "bidirectional"))
      (node (ref "U5") (pin "3") (pinfunction "CPGND_3") (pintype "bidirectional"))
      (node (ref "U5") (pin "9") (pinfunction "AGND_9") (pintype "bidirectional"))
      (node (ref "U6") (pin "GND") (pinfunction "GND_GND") (pintype "bidirectional"))
      (node (ref "USB") (pin "5") (pinfunction "GND_5") (pintype "bidirectional"))
    )
    (net (code "15") (name "GPIO_6") (class "Default")
      (node (ref "I_SLEEP") (pin "2") (pinfunction "2_2") (pintype "bidirectional"))
      (node (ref "J2") (pin "P$25") (pinfunction "GP6_P$25") (pintype "bidirectional"))
    )
    (net (code "16") (name "GPIO_12") (class "Default")
      (node (ref "J2") (pin "P$5") (pinfunction "GP12_P$5") (pintype "bidirectional"))
    )
    (net (code "17") (name "GPIO_CENTER") (class "Default")
      (node (ref "I_CENTER") (pin "3") (pinfunction "2_3") (pintype "passive"))
      (node (ref "I_CENTER") (pin "4") (pinfunction "2_4") (pintype "passive"))
      (node (ref "J2") (pin "P$33") (pinfunction "GP22_P$33") (pintype "bidirectional"))
    )
    (net (code "18") (name "GPIO_DOWN") (class "Default")
      (node (ref "I_DOWN") (pin "3") (pinfunction "2_3") (pintype "passive"))
      (node (ref "I_DOWN") (pin "4") (pinfunction "2_4") (pintype "passive"))
      (node (ref "J2") (pin "P$35") (pinfunction "GP17_P$35") (pintype "bidirectional"))
    )
    (net (code "19") (name "GPIO_LEFT") (class "Default")
      (node (ref "I_LEFT") (pin "3") (pinfunction "2_3") (pintype "passive"))
      (node (ref "I_LEFT") (pin "4") (pinfunction "2_4") (pintype "passive"))
      (node (ref "J2") (pin "P$26") (pinfunction "GP5_P$26") (pintype "bidirectional"))
    )
    (net (code "20") (name "GPIO_RIGHT") (class "Default")
      (node (ref "I_RIGHT") (pin "3") (pinfunction "2_3") (pintype "passive"))
      (node (ref "I_RIGHT") (pin "4") (pinfunction "2_4") (pintype "passive"))
      (node (ref "J2") (pin "P$34") (pinfunction "GP27_P$34") (pintype "bidirectional"))
    )
    (net (code "21") (name "GPIO_UP") (class "Default")
      (node (ref "I_UP") (pin "3") (pinfunction "2_3") (pintype "passive"))
      (node (ref "I_UP") (pin "4") (pinfunction "2_4") (pintype "passive"))
      (node (ref "J2") (pin "P$2") (pinfunction "GP20_P$2") (pintype "bidirectional"))
    )
    (net (code "22") (name "GPIO_VOL_DOWN") (class "Default")
      (node (ref "I_VOL_DOWN") (pin "2") (pinfunction "2_2") (pintype "bidirectional"))
      (node (ref "J2") (pin "P$24") (pinfunction "GP13_P$24") (pintype "bidirectional"))
    )
    (net (code "23") (name "GPIO_VOL_UP") (class "Default")
      (node (ref "I_VOL_UP") (pin "2") (pinfunction "2_2") (pintype "bidirectional"))
      (node (ref "J2") (pin "P$22") (pinfunction "GP26_P$22") (pintype "bidirectional"))
    )
    (net (code "24") (name "LCDCS_3V") (class "Default")
      (node (ref "DISP1") (pin "5") (pinfunction "CS_5") (pintype "input"))
      (node (ref "J2") (pin "P$9") (pinfunction "CE0_P$9") (pintype "output"))
    )
    (net (code "25") (name "LEDK") (class "Default")
      (node (ref "Q1") (pin "3") (pinfunction "C_3") (pintype "passive"))
      (node (ref "R12") (pin "1") (pinfunction "1_1") (pintype "passive"))
      (node (ref "R13") (pin "1") (pinfunction "1_1") (pintype "passive"))
      (node (ref "R14") (pin "1") (pinfunction "1_1") (pintype "passive"))
      (node (ref "R17") (pin "1") (pinfunction "1_1") (pintype "passive"))
    )
    (net (code "26") (name "MISO") (class "Default")
      (node (ref "DISP1") (pin "7") (pinfunction "MISO_7") (pintype "output"))
      (node (ref "J2") (pin "P$30") (pinfunction "MISO_P$30") (pintype "input"))
    )
    (net (code "27") (name "MOSI_3V") (class "Default")
      (node (ref "DISP1") (pin "6") (pinfunction "MOSI_6") (pintype "input"))
      (node (ref "J2") (pin "P$31") (pinfunction "MOSI_P$31") (pintype "output"))
    )
    (net (code "28") (name "Net-(C13-Pad2)") (class "Default")
      (node (ref "C13") (pin "2") (pinfunction "2_2") (pintype "passive"))
      (node (ref "J1") (pin "TIP") (pinfunction "TIP_TIP") (pintype "bidirectional"))
      (node (ref "R2") (pin "2") (pinfunction "2_2") (pintype "passive"))
    )
    (net (code "29") (name "Net-(C14-Pad2)") (class "Default")
      (node (ref "C14") (pin "2") (pinfunction "2_2") (pintype "passive"))
      (node (ref "J1") (pin "RING1") (pinfunction "RING1_RING1") (pintype "bidirectional"))
      (node (ref "R1") (pin "2") (pinfunction "2_2") (pintype "passive"))
    )
    (net (code "30") (name "Net-(D1-PadC)") (class "Default")
      (node (ref "D1") (pin "C") (pinfunction "C_C") (pintype "passive"))
      (node (ref "R9") (pin "2") (pinfunction "2_2") (pintype "passive"))
    )
    (net (code "31") (name "Net-(D2-PadC)") (class "Default")
      (node (ref "D2") (pin "C") (pinfunction "C_C") (pintype "passive"))
      (node (ref "R8") (pin "2") (pinfunction "2_2") (pintype "passive"))
    )
    (net (code "32") (name "Net-(DISP1-LEDK-Pad11)") (class "Default")
      (node (ref "DISP1") (pin "11") (pinfunction "LEDK_11") (pintype "power_in"))
      (node (ref "R12") (pin "2") (pinfunction "2_2") (pintype "passive"))
    )
    (net (code "33") (name "Net-(DISP1-LEDK-Pad12)") (class "Default")
      (node (ref "DISP1") (pin "12") (pinfunction "LEDK_12") (pintype "power_in"))
      (node (ref "R13") (pin "2") (pinfunction "2_2") (pintype "passive"))
    )
    (net (code "34") (name "Net-(DISP1-LEDK-Pad13)") (class "Default")
      (node (ref "DISP1") (pin "13") (pinfunction "LEDK_13") (pintype "power_in"))
      (node (ref "R14") (pin "2") (pinfunction "2_2") (pintype "passive"))
    )
    (net (code "35") (name "Net-(DISP1-LEDK-Pad14)") (class "Default")
      (node (ref "DISP1") (pin "14") (pinfunction "LEDK_14") (pintype "power_in"))
      (node (ref "R17") (pin "2") (pinfunction "2_2") (pintype "passive"))
    )
    (net (code "36") (name "Net-(Q1-B)") (class "Default")
      (node (ref "Q1") (pin "1") (pinfunction "B_1") (pintype "passive"))
      (node (ref "R15") (pin "2") (pinfunction "2_2") (pintype "passive"))
    )
    (net (code "37") (name "Net-(R10-Pad1)") (class "Default")
      (node (ref "R10") (pin "1") (pinfunction "1_1") (pintype "passive"))
      (node (ref "R11") (pin "2") (pinfunction "2_2") (pintype "passive"))
      (node (ref "U6") (pin "FB") (pinfunction "FB_FB") (pintype "bidirectional"))
    )
    (net (code "38") (name "Net-(RN1B-1)") (class "Default")
      (node (ref "RN1") (pin "2") (pinfunction "1_2") (pintype "passive"))
      (node (ref "U4") (pin "2") (pinfunction "ALERT_2") (pintype "bidirectional"))
    )
    (net (code "39") (name "Net-(S1-P)") (class "Default")
      (node (ref "C11") (pin "1") (pinfunction "1_1") (pintype "passive"))
      (node (ref "IN") (pin "TP") (pinfunction "TP_TP") (pintype "input"))
      (node (ref "L1") (pin "2") (pinfunction "2_2") (pintype "passive"))
      (node (ref "S1") (pin "2") (pinfunction "P_2") (pintype "passive"))
      (node (ref "U6") (pin "EN") (pinfunction "EN_EN") (pintype "bidirectional"))
      (node (ref "U6") (pin "IN") (pinfunction "IN_IN") (pintype "bidirectional"))
    )
    (net (code "40") (name "Net-(U$9-IN)") (class "Default")
      (node (ref "L1") (pin "1") (pinfunction "1_1") (pintype "passive"))
      (node (ref "U$9") (pin "1") (pinfunction "IN_1") (pintype "input"))
      (node (ref "U6") (pin "SW") (pinfunction "SW_SW") (pintype "bidirectional"))
    )
    (net (code "41") (name "Net-(U1-CS)") (class "Default")
      (node (ref "R5") (pin "2") (pinfunction "2_2") (pintype "passive"))
      (node (ref "U1") (pin "2") (pinfunction "CS_2") (pintype "input"))
    )
    (net (code "42") (name "Net-(U1-OC)") (class "Default")
      (node (ref "U1") (pin "3") (pinfunction "OC_3") (pintype "power_in"))
      (node (ref "U2") (pin "4") (pinfunction "G_4") (pintype "passive"))
    )
    (net (code "43") (name "Net-(U1-OD)") (class "Default")
      (node (ref "U1") (pin "1") (pinfunction "OD_1") (pintype "power_in"))
      (node (ref "U2") (pin "5") (pinfunction "G_5") (pintype "passive"))
    )
    (net (code "44") (name "Net-(U1-VCC)") (class "Default")
      (node (ref "C8") (pin "1") (pinfunction "1_1") (pintype "passive"))
      (node (ref "R7") (pin "1") (pinfunction "1_1") (pintype "passive"))
      (node (ref "U1") (pin "5") (pinfunction "VCC_5") (pintype "input"))
    )
    (net (code "45") (name "Net-(U2A-D)") (class "Default")
      (node (ref "U2") (pin "1") (pinfunction "D_1") (pintype "passive"))
      (node (ref "U2") (pin "8") (pinfunction "D_8") (pintype "passive"))
    )
    (net (code "46") (name "Net-(U3-CHRG)") (class "Default")
      (node (ref "R8") (pin "1") (pinfunction "1_1") (pintype "passive"))
      (node (ref "U3") (pin "7") (pinfunction "CHRG_7") (pintype "output"))
    )
    (net (code "47") (name "Net-(U3-PROG)") (class "Default")
      (node (ref "R6") (pin "2") (pinfunction "2_2") (pintype "passive"))
      (node (ref "U3") (pin "2") (pinfunction "PROG_2") (pintype "input"))
    )
    (net (code "48") (name "Net-(U3-STDBY)") (class "Default")
      (node (ref "R9") (pin "1") (pinfunction "1_1") (pintype "passive"))
      (node (ref "U3") (pin "6") (pinfunction "STDBY_6") (pintype "input"))
    )
    (net (code "49") (name "Net-(U4-ADDR)") (class "Default")
      (node (ref "RN1") (pin "1") (pinfunction "1_1") (pintype "passive"))
      (node (ref "U4") (pin "1") (pinfunction "ADDR_1") (pintype "bidirectional"))
    )
    (net (code "50") (name "Net-(U4-AIN2)") (class "Default")
      (node (ref "A3") (pin "TP") (pinfunction "TP_TP") (pintype "input"))
      (node (ref "U4") (pin "6") (pinfunction "AIN2_6") (pintype "bidirectional"))
    )
    (net (code "51") (name "Net-(U4-AIN3)") (class "Default")
      (node (ref "A2") (pin "TP") (pinfunction "TP_TP") (pintype "input"))
      (node (ref "U4") (pin "7") (pinfunction "AIN3_7") (pintype "bidirectional"))
    )
    (net (code "52") (name "Net-(U5-CAPM)") (class "Default")
      (node (ref "C15") (pin "2") (pinfunction "2_2") (pintype "passive"))
      (node (ref "U5") (pin "4") (pinfunction "CAPM_4") (pintype "bidirectional"))
    )
    (net (code "53") (name "Net-(U5-CAPP)") (class "Default")
      (node (ref "C15") (pin "1") (pinfunction "1_1") (pintype "passive"))
      (node (ref "U5") (pin "2") (pinfunction "CAPP_2") (pintype "bidirectional"))
    )
    (net (code "54") (name "Net-(U5-LDOO)") (class "Default")
      (node (ref "C1") (pin "2") (pinfunction "2_2") (pintype "passive"))
      (node (ref "U5") (pin "18") (pinfunction "LDOO_18") (pintype "bidirectional"))
    )
    (net (code "55") (name "Net-(U5-OUTL)") (class "Default")
      (node (ref "R1") (pin "1") (pinfunction "1_1") (pintype "passive"))
      (node (ref "U5") (pin "6") (pinfunction "OUTL_6") (pintype "bidirectional"))
    )
    (net (code "56") (name "Net-(U5-OUTR)") (class "Default")
      (node (ref "R2") (pin "1") (pinfunction "1_1") (pintype "passive"))
      (node (ref "U5") (pin "7") (pinfunction "OUTR_7") (pintype "bidirectional"))
    )
    (net (code "57") (name "Net-(U5-VNEG)") (class "Default")
      (node (ref "C2") (pin "1") (pinfunction "1_1") (pintype "passive"))
      (node (ref "U5") (pin "5") (pinfunction "VNEG_5") (pintype "bidirectional"))
    )
    (net (code "58") (name "RESET_3V") (class "Default")
      (node (ref "DISP1") (pin "2") (pinfunction "RESET_2") (pintype "input"))
      (node (ref "J2") (pin "P$10") (pinfunction "GP25_P$10") (pintype "bidirectional"))
    )
    (net (code "59") (name "SCL") (class "Default")
      (node (ref "J2") (pin "P$38") (pinfunction "SCL_P$38") (pintype "bidirectional"))
      (node (ref "RN1") (pin "4") (pinfunction "1_4") (pintype "passive"))
      (node (ref "U4") (pin "10") (pinfunction "SCL_10") (pintype "bidirectional"))
    )
    (net (code "60") (name "SCLK_3V") (class "Default")
      (node (ref "DISP1") (pin "3") (pinfunction "SCK_3") (pintype "input"))
      (node (ref "J2") (pin "P$29") (pinfunction "SCLK_P$29") (pintype "output"))
    )
    (net (code "61") (name "SDA") (class "Default")
      (node (ref "J2") (pin "P$39") (pinfunction "SDA_P$39") (pintype "bidirectional"))
      (node (ref "RN1") (pin "3") (pinfunction "1_3") (pintype "passive"))
      (node (ref "U4") (pin "9") (pinfunction "SDA_9") (pintype "bidirectional"))
    )
    (net (code "62") (name "VCC-ISO") (class "Default")
      (node (ref "C16") (pin "2") (pinfunction "2_2") (pintype "passive"))
      (node (ref "C3") (pin "1") (pinfunction "1_1") (pintype "passive"))
      (node (ref "C4") (pin "1") (pinfunction "1_1") (pintype "passive"))
      (node (ref "C6") (pin "1") (pinfunction "1_1") (pintype "passive"))
      (node (ref "C7") (pin "1") (pinfunction "1_1") (pintype "passive"))
      (node (ref "FB1") (pin "2") (pinfunction "2_2") (pintype "passive"))
      (node (ref "RN1") (pin "5") (pinfunction "2_5") (pintype "passive"))
      (node (ref "RN1") (pin "6") (pinfunction "2_6") (pintype "passive"))
      (node (ref "RN1") (pin "7") (pinfunction "2_7") (pintype "passive"))
      (node (ref "U4") (pin "8") (pinfunction "VDD_8") (pintype "bidirectional"))
      (node (ref "U5") (pin "1") (pinfunction "CPVDD_1") (pintype "bidirectional"))
      (node (ref "U5") (pin "17") (pinfunction "XSMT_17") (pintype "bidirectional"))
      (node (ref "U5") (pin "20") (pinfunction "DVDD_20") (pintype "bidirectional"))
      (node (ref "U5") (pin "8") (pinfunction "AVDD_8") (pintype "bidirectional"))
    )
    (net (code "63") (name "V_USB") (class "Default")
      (node (ref "C10") (pin "1") (pinfunction "1_1") (pintype "passive"))
      (node (ref "D1") (pin "A") (pinfunction "A_A") (pintype "passive"))
      (node (ref "D2") (pin "A") (pinfunction "A_A") (pintype "passive"))
      (node (ref "R18") (pin "2") (pinfunction "2_2") (pintype "passive"))
      (node (ref "S1") (pin "3") (pinfunction "S_3") (pintype "passive"))
      (node (ref "U3") (pin "4") (pinfunction "VCC_4") (pintype "power_in"))
      (node (ref "U3") (pin "8") (pinfunction "CE_8") (pintype "input"))
      (node (ref "USB") (pin "1") (pinfunction "VCC_1") (pintype "bidirectional"))
    )
    (net (code "64") (name "unconnected-(J2-CE1-PadP$8)") (class "Default")
      (node (ref "J2") (pin "P$8") (pinfunction "CE1_P$8") (pintype "output"))
    )
    (net (code "65") (name "unconnected-(J2-GP4-PadP$37)") (class "Default")
      (node (ref "J2") (pin "P$37") (pinfunction "GP4_P$37") (pintype "bidirectional"))
    )
    (net (code "66") (name "unconnected-(J2-GP16-PadP$3)") (class "Default")
      (node (ref "J2") (pin "P$3") (pinfunction "GP16_P$3") (pintype "bidirectional"))
    )
    (net (code "67") (name "unconnected-(J2-ID_SC-PadP$7)") (class "Default")
      (node (ref "J2") (pin "P$7") (pinfunction "ID_SC_P$7") (pintype "bidirectional"))
    )
    (net (code "68") (name "unconnected-(J2-ID_SD-PadP$27)") (class "Default")
      (node (ref "J2") (pin "P$27") (pinfunction "ID_SD_P$27") (pintype "bidirectional"))
    )
    (net (code "69") (name "unconnected-(J2-RXI-PadP$16)") (class "Default")
      (node (ref "J2") (pin "P$16") (pinfunction "RXI_P$16") (pintype "input"))
    )
    (net (code "70") (name "unconnected-(J2-TXO-PadP$17)") (class "Default")
      (node (ref "J2") (pin "P$17") (pinfunction "TXO_P$17") (pintype "output"))
    )
    (net (code "71") (name "unconnected-(U1-TD-Pad4)") (class "Default")
      (node (ref "U1") (pin "4") (pinfunction "TD_4") (pintype "output"))
    )
    (net (code "72") (name "unconnected-(U6-PadNC)") (class "Default")
      (node (ref "U6") (pin "NC") (pinfunction "NC_NC") (pintype "bidirectional"))
    )
    (net (code "73") (name "unconnected-(USB-ID-Pad4)") (class "Default")
      (node (ref "USB") (pin "4") (pinfunction "ID_4") (pintype "bidirectional"))
    )
  )
)
